# CAN-BUS-UART_v1.net
KiCad netlist of a schematic drawn in EAGLE
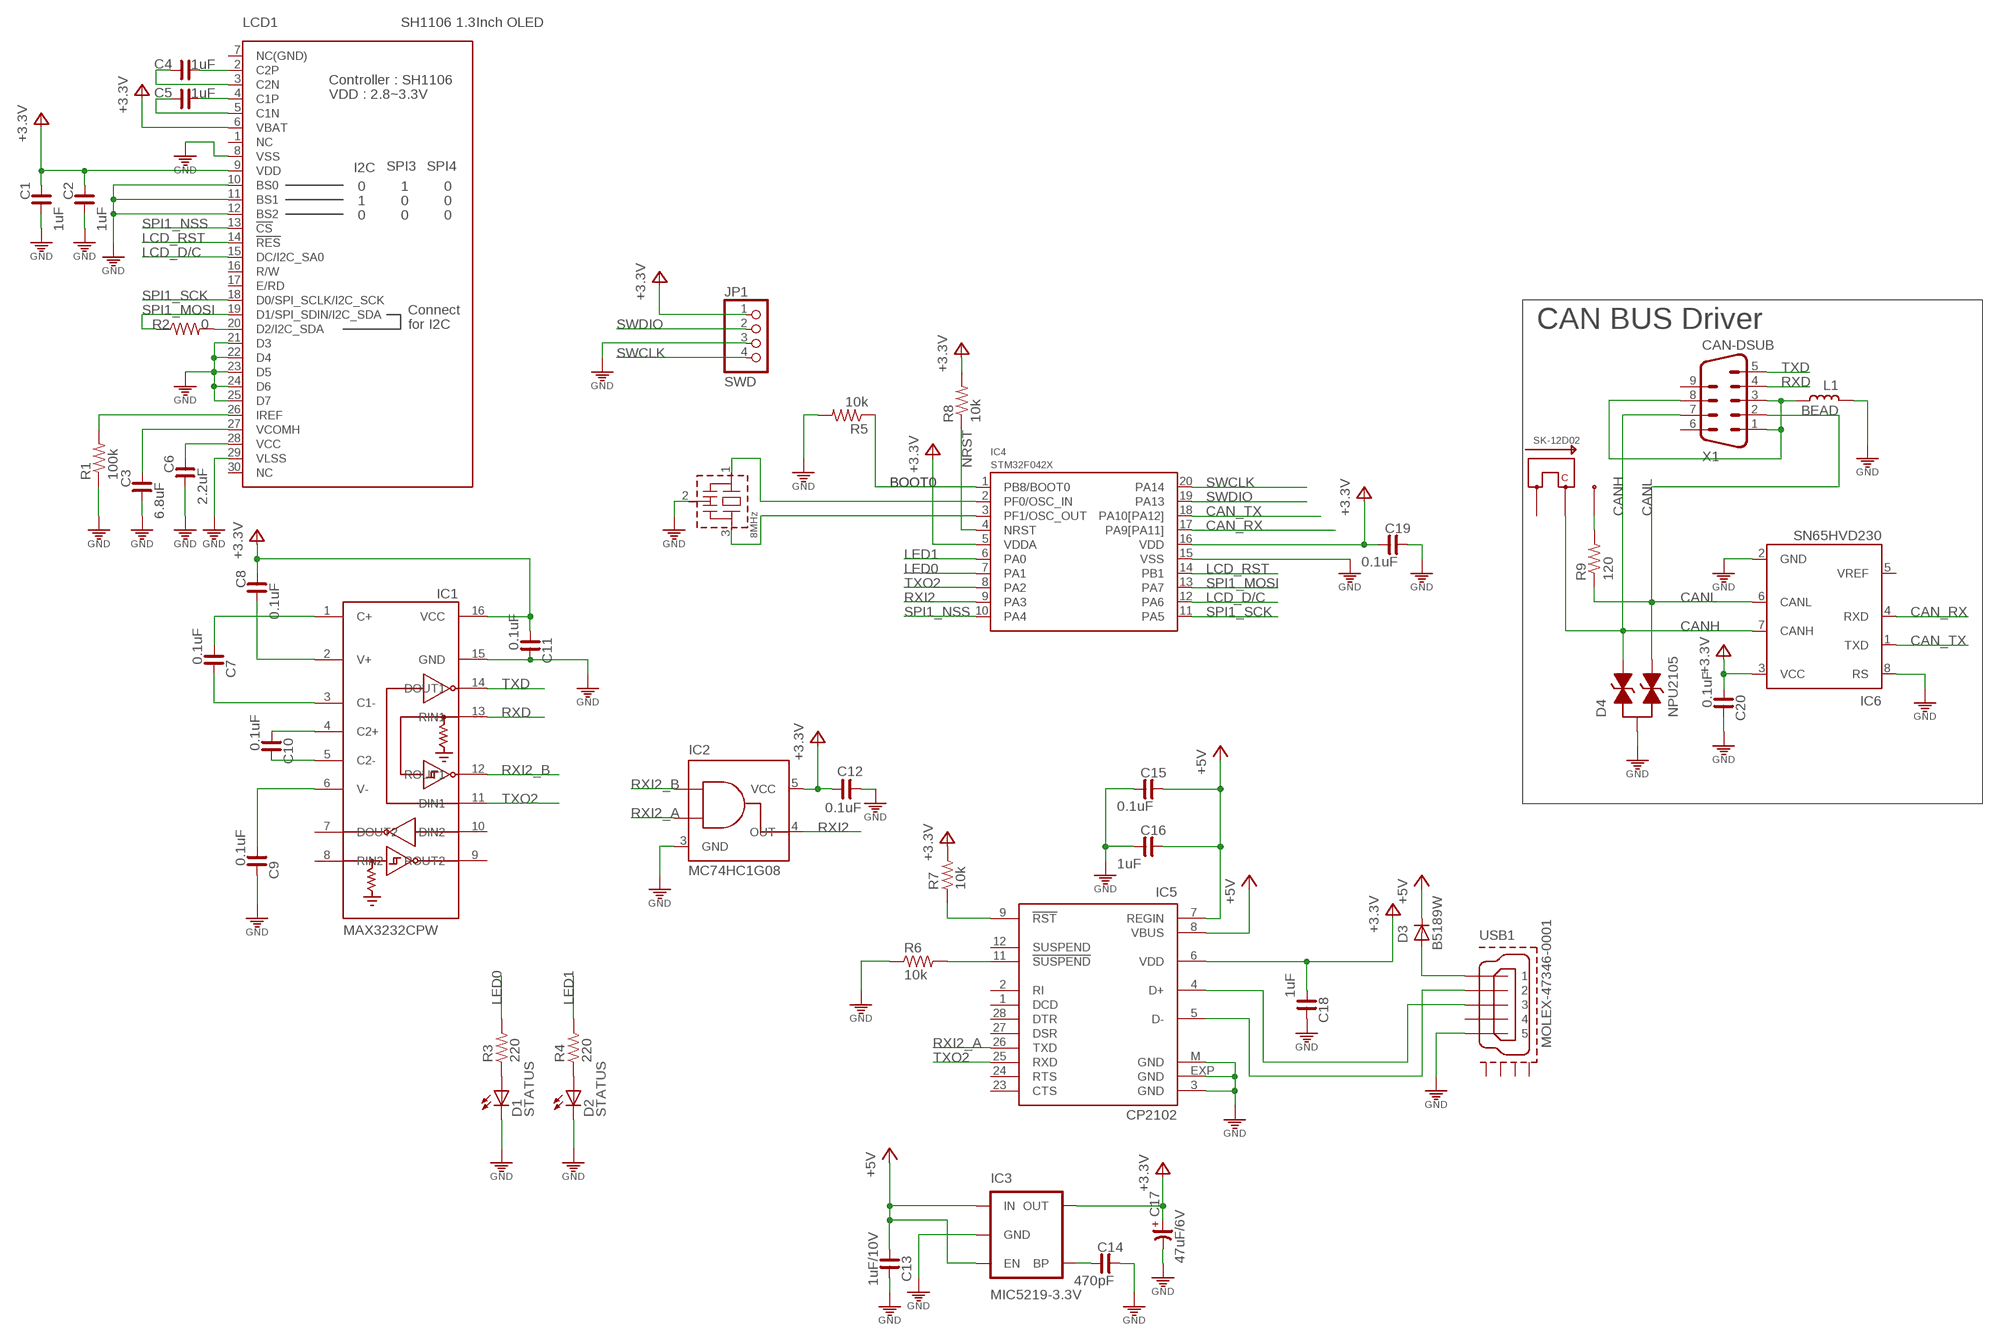
[diagram p0: schematic, sheet 1]

(export (version "E")
  (design (tool "Eeschema 10.0.6"))
  (components
    (comp (ref "C1")
      (value "1uF")
      (footprint "eagle-import:C0603")
      (libsource (lib "eagle-import") (part "C_0603"))
    )
    (comp (ref "C2")
      (value "1uF")
      (footprint "eagle-import:C0603")
      (libsource (lib "eagle-import") (part "C_0603"))
    )
    (comp (ref "C3")
      (value "6.8uF")
      (footprint "eagle-import:C0805")
      (libsource (lib "eagle-import") (part "C_0805"))
    )
    (comp (ref "C4")
      (value "1uF")
      (footprint "eagle-import:C0603")
      (libsource (lib "eagle-import") (part "C_0603"))
    )
    (comp (ref "C5")
      (value "1uF")
      (footprint "eagle-import:C0603")
      (libsource (lib "eagle-import") (part "C_0603"))
    )
    (comp (ref "C6")
      (value "2.2uF")
      (footprint "eagle-import:C0805")
      (libsource (lib "eagle-import") (part "C_0805"))
    )
    (comp (ref "C7")
      (value "0.1uF")
      (footprint "eagle-import:C0603")
      (libsource (lib "eagle-import") (part "C_0603"))
    )
    (comp (ref "C8")
      (value "0.1uF")
      (footprint "eagle-import:C0603")
      (libsource (lib "eagle-import") (part "C_0603"))
    )
    (comp (ref "C9")
      (value "0.1uF")
      (footprint "eagle-import:C0603")
      (libsource (lib "eagle-import") (part "C_0603"))
    )
    (comp (ref "C10")
      (value "0.1uF")
      (footprint "eagle-import:C0603")
      (libsource (lib "eagle-import") (part "C_0603"))
    )
    (comp (ref "C11")
      (value "0.1uF")
      (footprint "eagle-import:C0603")
      (libsource (lib "eagle-import") (part "C_0603"))
    )
    (comp (ref "C12")
      (value "0.1uF")
      (footprint "eagle-import:C0603")
      (libsource (lib "eagle-import") (part "C_0603"))
    )
    (comp (ref "C13")
      (value "1uF/10V")
      (footprint "eagle-import:C0603")
      (libsource (lib "eagle-import") (part "C_0603"))
    )
    (comp (ref "C14")
      (value "470pF")
      (footprint "eagle-import:C0603")
      (libsource (lib "eagle-import") (part "C_0603"))
    )
    (comp (ref "C15")
      (value "0.1uF")
      (footprint "eagle-import:C0603")
      (libsource (lib "eagle-import") (part "C_0603"))
    )
    (comp (ref "C16")
      (value "1uF")
      (footprint "eagle-import:C0603")
      (libsource (lib "eagle-import") (part "C_0603"))
    )
    (comp (ref "C17")
      (value "47uF/6V")
      (footprint "eagle-import:C3528-21_T")
      (libsource (lib "eagle-import") (part "CP_3528-21"))
    )
    (comp (ref "C18")
      (value "1uF")
      (footprint "eagle-import:C0603")
      (libsource (lib "eagle-import") (part "C_0603"))
    )
    (comp (ref "C19")
      (value "0.1uF")
      (footprint "eagle-import:C0603")
      (libsource (lib "eagle-import") (part "C_0603"))
    )
    (comp (ref "C20")
      (value "0.1uF")
      (footprint "eagle-import:C0603")
      (libsource (lib "eagle-import") (part "C_0603"))
    )
    (comp (ref "D1")
      (value "STATUS")
      (footprint "eagle-import:3FG2HD-T1")
      (libsource (lib "eagle-import") (part "LED3FG2HD-T1"))
    )
    (comp (ref "D2")
      (value "STATUS")
      (footprint "eagle-import:3FG2HD-T1")
      (libsource (lib "eagle-import") (part "LED3FG2HD-T1"))
    )
    (comp (ref "D3")
      (value "B5189W")
      (footprint "eagle-import:SOD323")
      (libsource (lib "eagle-import") (part "B5189WN"))
    )
    (comp (ref "D4")
      (value "NPU2105")
      (footprint "eagle-import:SOT23")
      (libsource (lib "eagle-import") (part "NPU2105"))
    )
    (comp (ref "IC1")
      (value "MAX3232CPW")
      (footprint "eagle-import:PW_R-PDSO-G16")
      (libsource (lib "eagle-import") (part "MAX3232MAX232CPW"))
    )
    (comp (ref "IC2")
      (value "MC74HC1G08")
      (footprint "eagle-import:SOT23-5L_MC74HC1G08")
      (libsource (lib "eagle-import") (part "AND_GATE_2INMC74HC1G08"))
    )
    (comp (ref "IC3")
      (value "MIC5219-3.3V")
      (footprint "eagle-import:SOT23-5")
      (libsource (lib "eagle-import") (part "V_REG_LDOSMD"))
    )
    (comp (ref "IC4")
      (value "STM32F042X")
      (footprint "eagle-import:TSSOP20")
      (libsource (lib "eagle-import") (part "STM32F042X"))
    )
    (comp (ref "IC5")
      (value "CP2102")
      (footprint "eagle-import:MLP28")
      (fields (field (name "MF") "FARNELL") (field (name "MPN") "CP2102-GM"))
      (libsource (lib "eagle-import") (part "CP2102"))
    )
    (comp (ref "IC6")
      (value "SN65HVD230")
      (footprint "eagle-import:SO8")
      (libsource (lib "eagle-import") (part "PCA82C250T"))
    )
    (comp (ref "JP1")
      (value "SWD")
      (footprint "eagle-import:1X04M")
      (libsource (lib "eagle-import") (part "PINHD-1X4M"))
    )
    (comp (ref "L1")
      (value "BEAD")
      (footprint "eagle-import:L0805")
      (libsource (lib "eagle-import") (part "L_0805"))
    )
    (comp (ref "LCD1")
      (value "SH1106 1.3Inch OLED")
      (footprint "eagle-import:SH1106_1.3OLED_BUTTOM")
      (libsource (lib "eagle-import") (part "SH1106_1.3_OLEDBUTTOM"))
    )
    (comp (ref "Q1")
      (value "8MHz")
      (footprint "eagle-import:CSTLA_X")
      (libsource (lib "eagle-import") (part "X-TAL-SMALLCSTCE16M00V53"))
    )
    (comp (ref "R1")
      (value "100k")
      (footprint "eagle-import:R0603@1")
      (libsource (lib "eagle-import") (part "R-US_R1608"))
    )
    (comp (ref "R2")
      (value "0")
      (footprint "eagle-import:R0603@1")
      (libsource (lib "eagle-import") (part "R-US_R1608"))
    )
    (comp (ref "R3")
      (value "220")
      (footprint "eagle-import:R0603")
      (libsource (lib "eagle-import") (part "R_0603"))
    )
    (comp (ref "R4")
      (value "220")
      (footprint "eagle-import:R0603")
      (libsource (lib "eagle-import") (part "R_0603"))
    )
    (comp (ref "R5")
      (value "10k")
      (footprint "eagle-import:R0603@1")
      (libsource (lib "eagle-import") (part "R-US_R1608"))
    )
    (comp (ref "R6")
      (value "10k")
      (footprint "eagle-import:R0603")
      (libsource (lib "eagle-import") (part "R_0603"))
    )
    (comp (ref "R7")
      (value "10k")
      (footprint "eagle-import:R0603")
      (libsource (lib "eagle-import") (part "R_0603"))
    )
    (comp (ref "R8")
      (value "10k")
      (footprint "eagle-import:R0603@1")
      (libsource (lib "eagle-import") (part "R-US_R1608"))
    )
    (comp (ref "R9")
      (value "120")
      (footprint "eagle-import:R0603@1")
      (libsource (lib "eagle-import") (part "R-US_R1608"))
    )
    (comp (ref "SW1")
      (value "SK-12D02")
      (footprint "eagle-import:SK-12DO2")
      (libsource (lib "eagle-import") (part "SW_2PSK-12D02"))
    )
    (comp (ref "USB1")
      (value "MOLEX-47346-0001")
      (footprint "eagle-import:MOLEX-47364-0001")
      (libsource (lib "eagle-import") (part "MOLEX-47346-0001"))
    )
    (comp (ref "X1")
      (value "CAN-DSUB")
      (footprint "eagle-import:M09H-1")
      (libsource (lib "eagle-import") (part "M09KR"))
    )
  )
  (nets
    (net (code "1") (name "+3V3") (class "Default")
      (node (ref "C1") (pin "1") (pinfunction "1_1") (pintype "passive"))
      (node (ref "C11") (pin "2") (pinfunction "2_2") (pintype "passive"))
      (node (ref "C12") (pin "2") (pinfunction "2_2") (pintype "passive"))
      (node (ref "C17") (pin "+") (pinfunction "+_+") (pintype "passive"))
      (node (ref "C18") (pin "2") (pinfunction "2_2") (pintype "passive"))
      (node (ref "C19") (pin "2") (pinfunction "2_2") (pintype "passive"))
      (node (ref "C2") (pin "1") (pinfunction "1_1") (pintype "passive"))
      (node (ref "C20") (pin "2") (pinfunction "2_2") (pintype "passive"))
      (node (ref "C8") (pin "1") (pinfunction "1_1") (pintype "passive"))
      (node (ref "IC1") (pin "16") (pinfunction "VCC_16") (pintype "power_in"))
      (node (ref "IC2") (pin "5") (pinfunction "VCC_5") (pintype "passive"))
      (node (ref "IC3") (pin "5") (pinfunction "OUT_5") (pintype "passive"))
      (node (ref "IC4") (pin "16") (pinfunction "VDD_16") (pintype "power_in"))
      (node (ref "IC4") (pin "5") (pinfunction "VDDA_5") (pintype "power_in"))
      (node (ref "IC5") (pin "6") (pinfunction "VDD_6") (pintype "power_in"))
      (node (ref "IC6") (pin "3") (pinfunction "VCC_3") (pintype "power_in"))
      (node (ref "JP1") (pin "1") (pinfunction "1_1") (pintype "passive"))
      (node (ref "LCD1") (pin "6") (pinfunction "VBAT_6") (pintype "passive"))
      (node (ref "LCD1") (pin "9") (pinfunction "VDD_9") (pintype "passive"))
      (node (ref "R7") (pin "2") (pinfunction "2_2") (pintype "passive"))
      (node (ref "R8") (pin "2") (pinfunction "2_2") (pintype "passive"))
    )
    (net (code "2") (name "+5V") (class "Default")
      (node (ref "C13") (pin "2") (pinfunction "2_2") (pintype "passive"))
      (node (ref "C15") (pin "1") (pinfunction "1_1") (pintype "passive"))
      (node (ref "C16") (pin "1") (pinfunction "1_1") (pintype "passive"))
      (node (ref "D3") (pin "C") (pinfunction "C_C") (pintype "passive"))
      (node (ref "IC3") (pin "1") (pinfunction "IN_1") (pintype "input"))
      (node (ref "IC3") (pin "3") (pinfunction "EN_3") (pintype "input"))
      (node (ref "IC5") (pin "7") (pinfunction "REGIN_7") (pintype "passive"))
      (node (ref "IC5") (pin "8") (pinfunction "VBUS_8") (pintype "input"))
    )
    (net (code "3") (name "/BOOT0") (class "Default")
      (node (ref "IC4") (pin "1") (pinfunction "PB8/BOOT0_1") (pintype "bidirectional"))
      (node (ref "R5") (pin "1") (pinfunction "1_1") (pintype "passive"))
    )
    (net (code "4") (name "/CANH") (class "Default")
      (node (ref "D4") (pin "G") (pinfunction "PIN1_G") (pintype "passive"))
      (node (ref "IC6") (pin "7") (pinfunction "CANH_7") (pintype "bidirectional"))
      (node (ref "SW1") (pin "C") (pinfunction "2_C") (pintype "bidirectional"))
      (node (ref "X1") (pin "7") (pinfunction "7_7") (pintype "passive"))
    )
    (net (code "5") (name "/CANL") (class "Default")
      (node (ref "D4") (pin "S") (pinfunction "PIN2_S") (pintype "passive"))
      (node (ref "IC6") (pin "6") (pinfunction "CANL_6") (pintype "bidirectional"))
      (node (ref "R9") (pin "1") (pinfunction "1_1") (pintype "passive"))
      (node (ref "X1") (pin "2") (pinfunction "2_2") (pintype "passive"))
    )
    (net (code "6") (name "/CAN_RX") (class "Default")
      (node (ref "IC4") (pin "17") (pinfunction "PA9[PA11]_17") (pintype "bidirectional"))
      (node (ref "IC6") (pin "4") (pinfunction "RXD_4") (pintype "output"))
    )
    (net (code "7") (name "/CAN_TX") (class "Default")
      (node (ref "IC4") (pin "18") (pinfunction "PA10[PA12]_18") (pintype "bidirectional"))
      (node (ref "IC6") (pin "1") (pinfunction "TXD_1") (pintype "input"))
    )
    (net (code "8") (name "/LCD_D{slash}C") (class "Default")
      (node (ref "IC4") (pin "12") (pinfunction "PA6_12") (pintype "bidirectional"))
      (node (ref "LCD1") (pin "15") (pinfunction "DC/I2C_SA0_15") (pintype "passive"))
    )
    (net (code "9") (name "/LCD_RST") (class "Default")
      (node (ref "IC4") (pin "14") (pinfunction "PB1_14") (pintype "bidirectional"))
      (node (ref "LCD1") (pin "14") (pinfunction "~{RES}_14") (pintype "passive"))
    )
    (net (code "10") (name "/LED0") (class "Default")
      (node (ref "IC4") (pin "7") (pinfunction "PA1_7") (pintype "bidirectional"))
      (node (ref "R3") (pin "2") (pinfunction "2_2") (pintype "passive"))
    )
    (net (code "11") (name "/LED1") (class "Default")
      (node (ref "IC4") (pin "6") (pinfunction "PA0_6") (pintype "bidirectional"))
      (node (ref "R4") (pin "2") (pinfunction "2_2") (pintype "passive"))
    )
    (net (code "12") (name "/NRST") (class "Default")
      (node (ref "IC4") (pin "4") (pinfunction "NRST_4") (pintype "bidirectional"))
      (node (ref "R8") (pin "1") (pinfunction "1_1") (pintype "passive"))
    )
    (net (code "13") (name "/RXD") (class "Default")
      (node (ref "IC1") (pin "13") (pinfunction "RIN1_13") (pintype "input"))
      (node (ref "X1") (pin "4") (pinfunction "4_4") (pintype "passive"))
    )
    (net (code "14") (name "/RXI2") (class "Default")
      (node (ref "IC2") (pin "4") (pinfunction "OUT_4") (pintype "output"))
      (node (ref "IC4") (pin "9") (pinfunction "PA3_9") (pintype "bidirectional"))
    )
    (net (code "15") (name "/RXI2_A") (class "Default")
      (node (ref "IC2") (pin "2") (pinfunction "INA_2") (pintype "input"))
      (node (ref "IC5") (pin "26") (pinfunction "TXD_26") (pintype "output"))
    )
    (net (code "16") (name "/RXI2_B") (class "Default")
      (node (ref "IC1") (pin "12") (pinfunction "ROUT1_12") (pintype "input"))
      (node (ref "IC2") (pin "1") (pinfunction "INB_1") (pintype "input"))
    )
    (net (code "17") (name "/SPI1_MOSI") (class "Default")
      (node (ref "IC4") (pin "13") (pinfunction "PA7_13") (pintype "bidirectional"))
      (node (ref "LCD1") (pin "19") (pinfunction "D1/SPI_SDIN/I2C_SDA_19") (pintype "passive"))
      (node (ref "R2") (pin "1") (pinfunction "1_1") (pintype "passive"))
    )
    (net (code "18") (name "/SPI1_NSS") (class "Default")
      (node (ref "IC4") (pin "10") (pinfunction "PA4_10") (pintype "bidirectional"))
      (node (ref "LCD1") (pin "13") (pinfunction "~{CS}_13") (pintype "passive"))
    )
    (net (code "19") (name "/SPI1_SCK") (class "Default")
      (node (ref "IC4") (pin "11") (pinfunction "PA5_11") (pintype "bidirectional"))
      (node (ref "LCD1") (pin "18") (pinfunction "D0/SPI_SCLK/I2C_SCK_18") (pintype "passive"))
    )
    (net (code "20") (name "/SWCLK") (class "Default")
      (node (ref "IC4") (pin "20") (pinfunction "PA14_20") (pintype "bidirectional"))
      (node (ref "JP1") (pin "4") (pinfunction "4_4") (pintype "passive"))
    )
    (net (code "21") (name "/SWDIO") (class "Default")
      (node (ref "IC4") (pin "19") (pinfunction "PA13_19") (pintype "bidirectional"))
      (node (ref "JP1") (pin "2") (pinfunction "2_2") (pintype "passive"))
    )
    (net (code "22") (name "/TXD") (class "Default")
      (node (ref "IC1") (pin "14") (pinfunction "DOUT1_14") (pintype "output"))
      (node (ref "X1") (pin "5") (pinfunction "5_5") (pintype "passive"))
    )
    (net (code "23") (name "/TXO2") (class "Default")
      (node (ref "IC1") (pin "11") (pinfunction "DIN1_11") (pintype "input"))
      (node (ref "IC4") (pin "8") (pinfunction "PA2_8") (pintype "bidirectional"))
      (node (ref "IC5") (pin "25") (pinfunction "RXD_25") (pintype "input"))
    )
    (net (code "24") (name "GND") (class "Default")
      (node (ref "C1") (pin "2") (pinfunction "2_2") (pintype "passive"))
      (node (ref "C11") (pin "1") (pinfunction "1_1") (pintype "passive"))
      (node (ref "C12") (pin "1") (pinfunction "1_1") (pintype "passive"))
      (node (ref "C13") (pin "1") (pinfunction "1_1") (pintype "passive"))
      (node (ref "C14") (pin "1") (pinfunction "1_1") (pintype "passive"))
      (node (ref "C15") (pin "2") (pinfunction "2_2") (pintype "passive"))
      (node (ref "C16") (pin "2") (pinfunction "2_2") (pintype "passive"))
      (node (ref "C17") (pin "-") (pinfunction "-_-") (pintype "passive"))
      (node (ref "C18") (pin "1") (pinfunction "1_1") (pintype "passive"))
      (node (ref "C19") (pin "1") (pinfunction "1_1") (pintype "passive"))
      (node (ref "C2") (pin "2") (pinfunction "2_2") (pintype "passive"))
      (node (ref "C20") (pin "1") (pinfunction "1_1") (pintype "passive"))
      (node (ref "C3") (pin "2") (pinfunction "2_2") (pintype "passive"))
      (node (ref "C6") (pin "2") (pinfunction "2_2") (pintype "passive"))
      (node (ref "C9") (pin "1") (pinfunction "1_1") (pintype "passive"))
      (node (ref "D1") (pin "K") (pinfunction "C_K") (pintype "passive"))
      (node (ref "D2") (pin "K") (pinfunction "C_K") (pintype "passive"))
      (node (ref "D4") (pin "D") (pinfunction "PIN3_D") (pintype "passive"))
      (node (ref "IC1") (pin "15") (pinfunction "GND_15") (pintype "power_in"))
      (node (ref "IC2") (pin "3") (pinfunction "GND_3") (pintype "passive"))
      (node (ref "IC3") (pin "2") (pinfunction "GND_2") (pintype "input"))
      (node (ref "IC4") (pin "15") (pinfunction "VSS_15") (pintype "power_in"))
      (node (ref "IC5") (pin "3") (pinfunction "GND_3") (pintype "power_in"))
      (node (ref "IC5") (pin "EXP") (pinfunction "GND_EXP") (pintype "power_in"))
      (node (ref "IC5") (pin "M") (pinfunction "GND_M") (pintype "power_in"))
      (node (ref "IC6") (pin "2") (pinfunction "GND_2") (pintype "power_in"))
      (node (ref "IC6") (pin "8") (pinfunction "RS_8") (pintype "input"))
      (node (ref "JP1") (pin "3") (pinfunction "3_3") (pintype "passive"))
      (node (ref "L1") (pin "2") (pinfunction "2_2") (pintype "passive"))
      (node (ref "LCD1") (pin "10") (pinfunction "BS0_10") (pintype "passive"))
      (node (ref "LCD1") (pin "11") (pinfunction "BS1_11") (pintype "passive"))
      (node (ref "LCD1") (pin "12") (pinfunction "BS2_12") (pintype "passive"))
      (node (ref "LCD1") (pin "21") (pinfunction "D3_21") (pintype "passive"))
      (node (ref "LCD1") (pin "22") (pinfunction "D4_22") (pintype "passive"))
      (node (ref "LCD1") (pin "23") (pinfunction "D5_23") (pintype "passive"))
      (node (ref "LCD1") (pin "24") (pinfunction "D6_24") (pintype "passive"))
      (node (ref "LCD1") (pin "25") (pinfunction "D7_25") (pintype "passive"))
      (node (ref "LCD1") (pin "29") (pinfunction "VLSS_29") (pintype "passive"))
      (node (ref "LCD1") (pin "8") (pinfunction "VSS_8") (pintype "passive"))
      (node (ref "Q1") (pin "2") (pinfunction "GND_2") (pintype "power_in"))
      (node (ref "R1") (pin "1") (pinfunction "1_1") (pintype "passive"))
      (node (ref "R5") (pin "2") (pinfunction "2_2") (pintype "passive"))
      (node (ref "R6") (pin "1") (pinfunction "1_1") (pintype "passive"))
      (node (ref "USB1") (pin "5") (pinfunction "5_5") (pintype "input"))
    )
    (net (code "25") (name "Net-(D1-PadA)") (class "Default")
      (node (ref "D1") (pin "A") (pinfunction "A_A") (pintype "passive"))
      (node (ref "R3") (pin "1") (pinfunction "1_1") (pintype "passive"))
    )
    (net (code "26") (name "Net-(D2-PadA)") (class "Default")
      (node (ref "D2") (pin "A") (pinfunction "A_A") (pintype "passive"))
      (node (ref "R4") (pin "1") (pinfunction "1_1") (pintype "passive"))
    )
    (net (code "27") (name "Net-(D3-PadA)") (class "Default")
      (node (ref "D3") (pin "A") (pinfunction "A_A") (pintype "passive"))
      (node (ref "USB1") (pin "1") (pinfunction "1_1") (pintype "input"))
    )
    (net (code "28") (name "Net-(IC1-C+)") (class "Default")
      (node (ref "C7") (pin "2") (pinfunction "2_2") (pintype "passive"))
      (node (ref "IC1") (pin "1") (pinfunction "C+_1") (pintype "passive"))
    )
    (net (code "29") (name "Net-(IC1-C1-)") (class "Default")
      (node (ref "C7") (pin "1") (pinfunction "1_1") (pintype "passive"))
      (node (ref "IC1") (pin "3") (pinfunction "C1-_3") (pintype "power_in"))
    )
    (net (code "30") (name "Net-(IC1-C2+)") (class "Default")
      (node (ref "C10") (pin "2") (pinfunction "2_2") (pintype "passive"))
      (node (ref "IC1") (pin "4") (pinfunction "C2+_4") (pintype "passive"))
    )
    (net (code "31") (name "Net-(IC1-C2-)") (class "Default")
      (node (ref "C10") (pin "1") (pinfunction "1_1") (pintype "passive"))
      (node (ref "IC1") (pin "5") (pinfunction "C2-_5") (pintype "passive"))
    )
    (net (code "32") (name "Net-(IC1-V+)") (class "Default")
      (node (ref "C8") (pin "2") (pinfunction "2_2") (pintype "passive"))
      (node (ref "IC1") (pin "2") (pinfunction "V+_2") (pintype "passive"))
    )
    (net (code "33") (name "Net-(IC1-V-)") (class "Default")
      (node (ref "C9") (pin "2") (pinfunction "2_2") (pintype "passive"))
      (node (ref "IC1") (pin "6") (pinfunction "V-_6") (pintype "passive"))
    )
    (net (code "34") (name "Net-(IC3-BP)") (class "Default")
      (node (ref "C14") (pin "2") (pinfunction "2_2") (pintype "passive"))
      (node (ref "IC3") (pin "4") (pinfunction "BP_4") (pintype "input"))
    )
    (net (code "35") (name "Net-(IC4-PF0{slash}OSC_IN)") (class "Default")
      (node (ref "IC4") (pin "2") (pinfunction "PF0/OSC_IN_2") (pintype "bidirectional"))
      (node (ref "Q1") (pin "1") (pinfunction "IN_1") (pintype "output"))
    )
    (net (code "36") (name "Net-(IC4-PF1{slash}OSC_OUT)") (class "Default")
      (node (ref "IC4") (pin "3") (pinfunction "PF1/OSC_OUT_3") (pintype "bidirectional"))
      (node (ref "Q1") (pin "3") (pinfunction "OUT_3") (pintype "input"))
    )
    (net (code "37") (name "Net-(IC5-D+)") (class "Default")
      (node (ref "IC5") (pin "4") (pinfunction "D+_4") (pintype "bidirectional"))
      (node (ref "USB1") (pin "3") (pinfunction "3_3") (pintype "input"))
    )
    (net (code "38") (name "Net-(IC5-D-)") (class "Default")
      (node (ref "IC5") (pin "5") (pinfunction "D-_5") (pintype "bidirectional"))
      (node (ref "USB1") (pin "2") (pinfunction "2_2") (pintype "input"))
    )
    (net (code "39") (name "Net-(IC5-~{RST})") (class "Default")
      (node (ref "IC5") (pin "9") (pinfunction "~{RST}_9") (pintype "bidirectional"))
      (node (ref "R7") (pin "1") (pinfunction "1_1") (pintype "passive"))
    )
    (net (code "40") (name "Net-(IC5-~{SUSPEND})") (class "Default")
      (node (ref "IC5") (pin "11") (pinfunction "~{SUSPEND}_11") (pintype "output"))
      (node (ref "R6") (pin "2") (pinfunction "2_2") (pintype "passive"))
    )
    (net (code "41") (name "Net-(L1-Pad1)") (class "Default")
      (node (ref "L1") (pin "1") (pinfunction "1_1") (pintype "passive"))
      (node (ref "X1") (pin "1") (pinfunction "1_1") (pintype "passive"))
      (node (ref "X1") (pin "3") (pinfunction "3_3") (pintype "passive"))
      (node (ref "X1") (pin "8") (pinfunction "8_8") (pintype "passive"))
    )
    (net (code "42") (name "Net-(LCD1-C1N)") (class "Default")
      (node (ref "C5") (pin "1") (pinfunction "1_1") (pintype "passive"))
      (node (ref "LCD1") (pin "5") (pinfunction "C1N_5") (pintype "passive"))
    )
    (net (code "43") (name "Net-(LCD1-C1P)") (class "Default")
      (node (ref "C5") (pin "2") (pinfunction "2_2") (pintype "passive"))
      (node (ref "LCD1") (pin "4") (pinfunction "C1P_4") (pintype "passive"))
    )
    (net (code "44") (name "Net-(LCD1-C2N)") (class "Default")
      (node (ref "C4") (pin "1") (pinfunction "1_1") (pintype "passive"))
      (node (ref "LCD1") (pin "3") (pinfunction "C2N_3") (pintype "passive"))
    )
    (net (code "45") (name "Net-(LCD1-C2P)") (class "Default")
      (node (ref "C4") (pin "2") (pinfunction "2_2") (pintype "passive"))
      (node (ref "LCD1") (pin "2") (pinfunction "C2P_2") (pintype "passive"))
    )
    (net (code "46") (name "Net-(LCD1-D2{slash}I2C_SDA)") (class "Default")
      (node (ref "LCD1") (pin "20") (pinfunction "D2/I2C_SDA_20") (pintype "passive"))
      (node (ref "R2") (pin "2") (pinfunction "2_2") (pintype "passive"))
    )
    (net (code "47") (name "Net-(LCD1-IREF)") (class "Default")
      (node (ref "LCD1") (pin "26") (pinfunction "IREF_26") (pintype "passive"))
      (node (ref "R1") (pin "2") (pinfunction "2_2") (pintype "passive"))
    )
    (net (code "48") (name "Net-(LCD1-VCC)") (class "Default")
      (node (ref "C6") (pin "1") (pinfunction "1_1") (pintype "passive"))
      (node (ref "LCD1") (pin "28") (pinfunction "VCC_28") (pintype "passive"))
    )
    (net (code "49") (name "Net-(LCD1-VCOMH)") (class "Default")
      (node (ref "C3") (pin "1") (pinfunction "1_1") (pintype "passive"))
      (node (ref "LCD1") (pin "27") (pinfunction "VCOMH_27") (pintype "passive"))
    )
    (net (code "50") (name "Net-(R9-Pad2)") (class "Default")
      (node (ref "R9") (pin "2") (pinfunction "2_2") (pintype "passive"))
      (node (ref "SW1") (pin "3") (pinfunction "3_3") (pintype "bidirectional"))
    )
    (net (code "51") (name "unconnected-(IC1-DIN2-Pad10)") (class "Default")
      (node (ref "IC1") (pin "10") (pinfunction "DIN2_10") (pintype "input"))
    )
    (net (code "52") (name "unconnected-(IC1-DOUT2-Pad7)") (class "Default")
      (node (ref "IC1") (pin "7") (pinfunction "DOUT2_7") (pintype "output"))
    )
    (net (code "53") (name "unconnected-(IC1-RIN2-Pad8)") (class "Default")
      (node (ref "IC1") (pin "8") (pinfunction "RIN2_8") (pintype "input"))
    )
    (net (code "54") (name "unconnected-(IC1-ROUT2-Pad9)") (class "Default")
      (node (ref "IC1") (pin "9") (pinfunction "ROUT2_9") (pintype "output"))
    )
    (net (code "55") (name "unconnected-(IC5-CTS-Pad23)") (class "Default")
      (node (ref "IC5") (pin "23") (pinfunction "CTS_23") (pintype "input"))
    )
    (net (code "56") (name "unconnected-(IC5-DCD-Pad1)") (class "Default")
      (node (ref "IC5") (pin "1") (pinfunction "DCD_1") (pintype "input"))
    )
    (net (code "57") (name "unconnected-(IC5-DSR-Pad27)") (class "Default")
      (node (ref "IC5") (pin "27") (pinfunction "DSR_27") (pintype "input"))
    )
    (net (code "58") (name "unconnected-(IC5-DTR-Pad28)") (class "Default")
      (node (ref "IC5") (pin "28") (pinfunction "DTR_28") (pintype "output"))
    )
    (net (code "59") (name "unconnected-(IC5-RI-Pad2)") (class "Default")
      (node (ref "IC5") (pin "2") (pinfunction "RI_2") (pintype "input"))
    )
    (net (code "60") (name "unconnected-(IC5-RTS-Pad24)") (class "Default")
      (node (ref "IC5") (pin "24") (pinfunction "RTS_24") (pintype "output"))
    )
    (net (code "61") (name "unconnected-(IC5-SUSPEND-Pad12)") (class "Default")
      (node (ref "IC5") (pin "12") (pinfunction "SUSPEND_12") (pintype "output"))
    )
    (net (code "62") (name "unconnected-(IC6-VREF-Pad5)") (class "Default")
      (node (ref "IC6") (pin "5") (pinfunction "VREF_5") (pintype "output"))
    )
    (net (code "63") (name "unconnected-(LCD1-E{slash}RD-Pad17)") (class "Default")
      (node (ref "LCD1") (pin "17") (pinfunction "E/RD_17") (pintype "passive"))
    )
    (net (code "64") (name "unconnected-(LCD1-NC(GND)-Pad7)") (class "Default")
      (node (ref "LCD1") (pin "7") (pinfunction "NC(GND)_7") (pintype "passive"))
    )
    (net (code "65") (name "unconnected-(LCD1-NC-Pad1)") (class "Default")
      (node (ref "LCD1") (pin "1") (pinfunction "NC_1") (pintype "no_connect"))
    )
    (net (code "66") (name "unconnected-(LCD1-NC-Pad30)") (class "Default")
      (node (ref "LCD1") (pin "30") (pinfunction "NC_30") (pintype "passive"))
    )
    (net (code "67") (name "unconnected-(LCD1-R{slash}W-Pad16)") (class "Default")
      (node (ref "LCD1") (pin "16") (pinfunction "R/W_16") (pintype "passive"))
    )
    (net (code "68") (name "unconnected-(SW1-Pad1)") (class "Default")
      (node (ref "SW1") (pin "1") (pinfunction "1_1") (pintype "bidirectional"))
    )
    (net (code "69") (name "unconnected-(USB1-Pad4)") (class "Default")
      (node (ref "USB1") (pin "4") (pinfunction "4_4") (pintype "input"))
    )
    (net (code "70") (name "unconnected-(USB1-PadGND1)") (class "Default")
      (node (ref "USB1") (pin "GND1") (pinfunction "GND1_GND1") (pintype "bidirectional"))
    )
    (net (code "71") (name "unconnected-(USB1-PadGND2)") (class "Default")
      (node (ref "USB1") (pin "GND2") (pinfunction "GND2_GND2") (pintype "bidirectional"))
    )
    (net (code "72") (name "unconnected-(USB1-PadGND3)") (class "Default")
      (node (ref "USB1") (pin "GND3") (pinfunction "GND3_GND3") (pintype "bidirectional"))
    )
    (net (code "73") (name "unconnected-(USB1-PadGND4)") (class "Default")
      (node (ref "USB1") (pin "GND4") (pinfunction "GND4_GND4") (pintype "bidirectional"))
    )
    (net (code "74") (name "unconnected-(X1-Pad6)") (class "Default")
      (node (ref "X1") (pin "6") (pinfunction "6_6") (pintype "passive"))
    )
    (net (code "75") (name "unconnected-(X1-Pad9)") (class "Default")
      (node (ref "X1") (pin "9") (pinfunction "9_9") (pintype "passive"))
    )
  )
)
